# Wedding_Centerpiece_Controller_V1_0.net
KiCad netlist of a schematic drawn in EAGLE
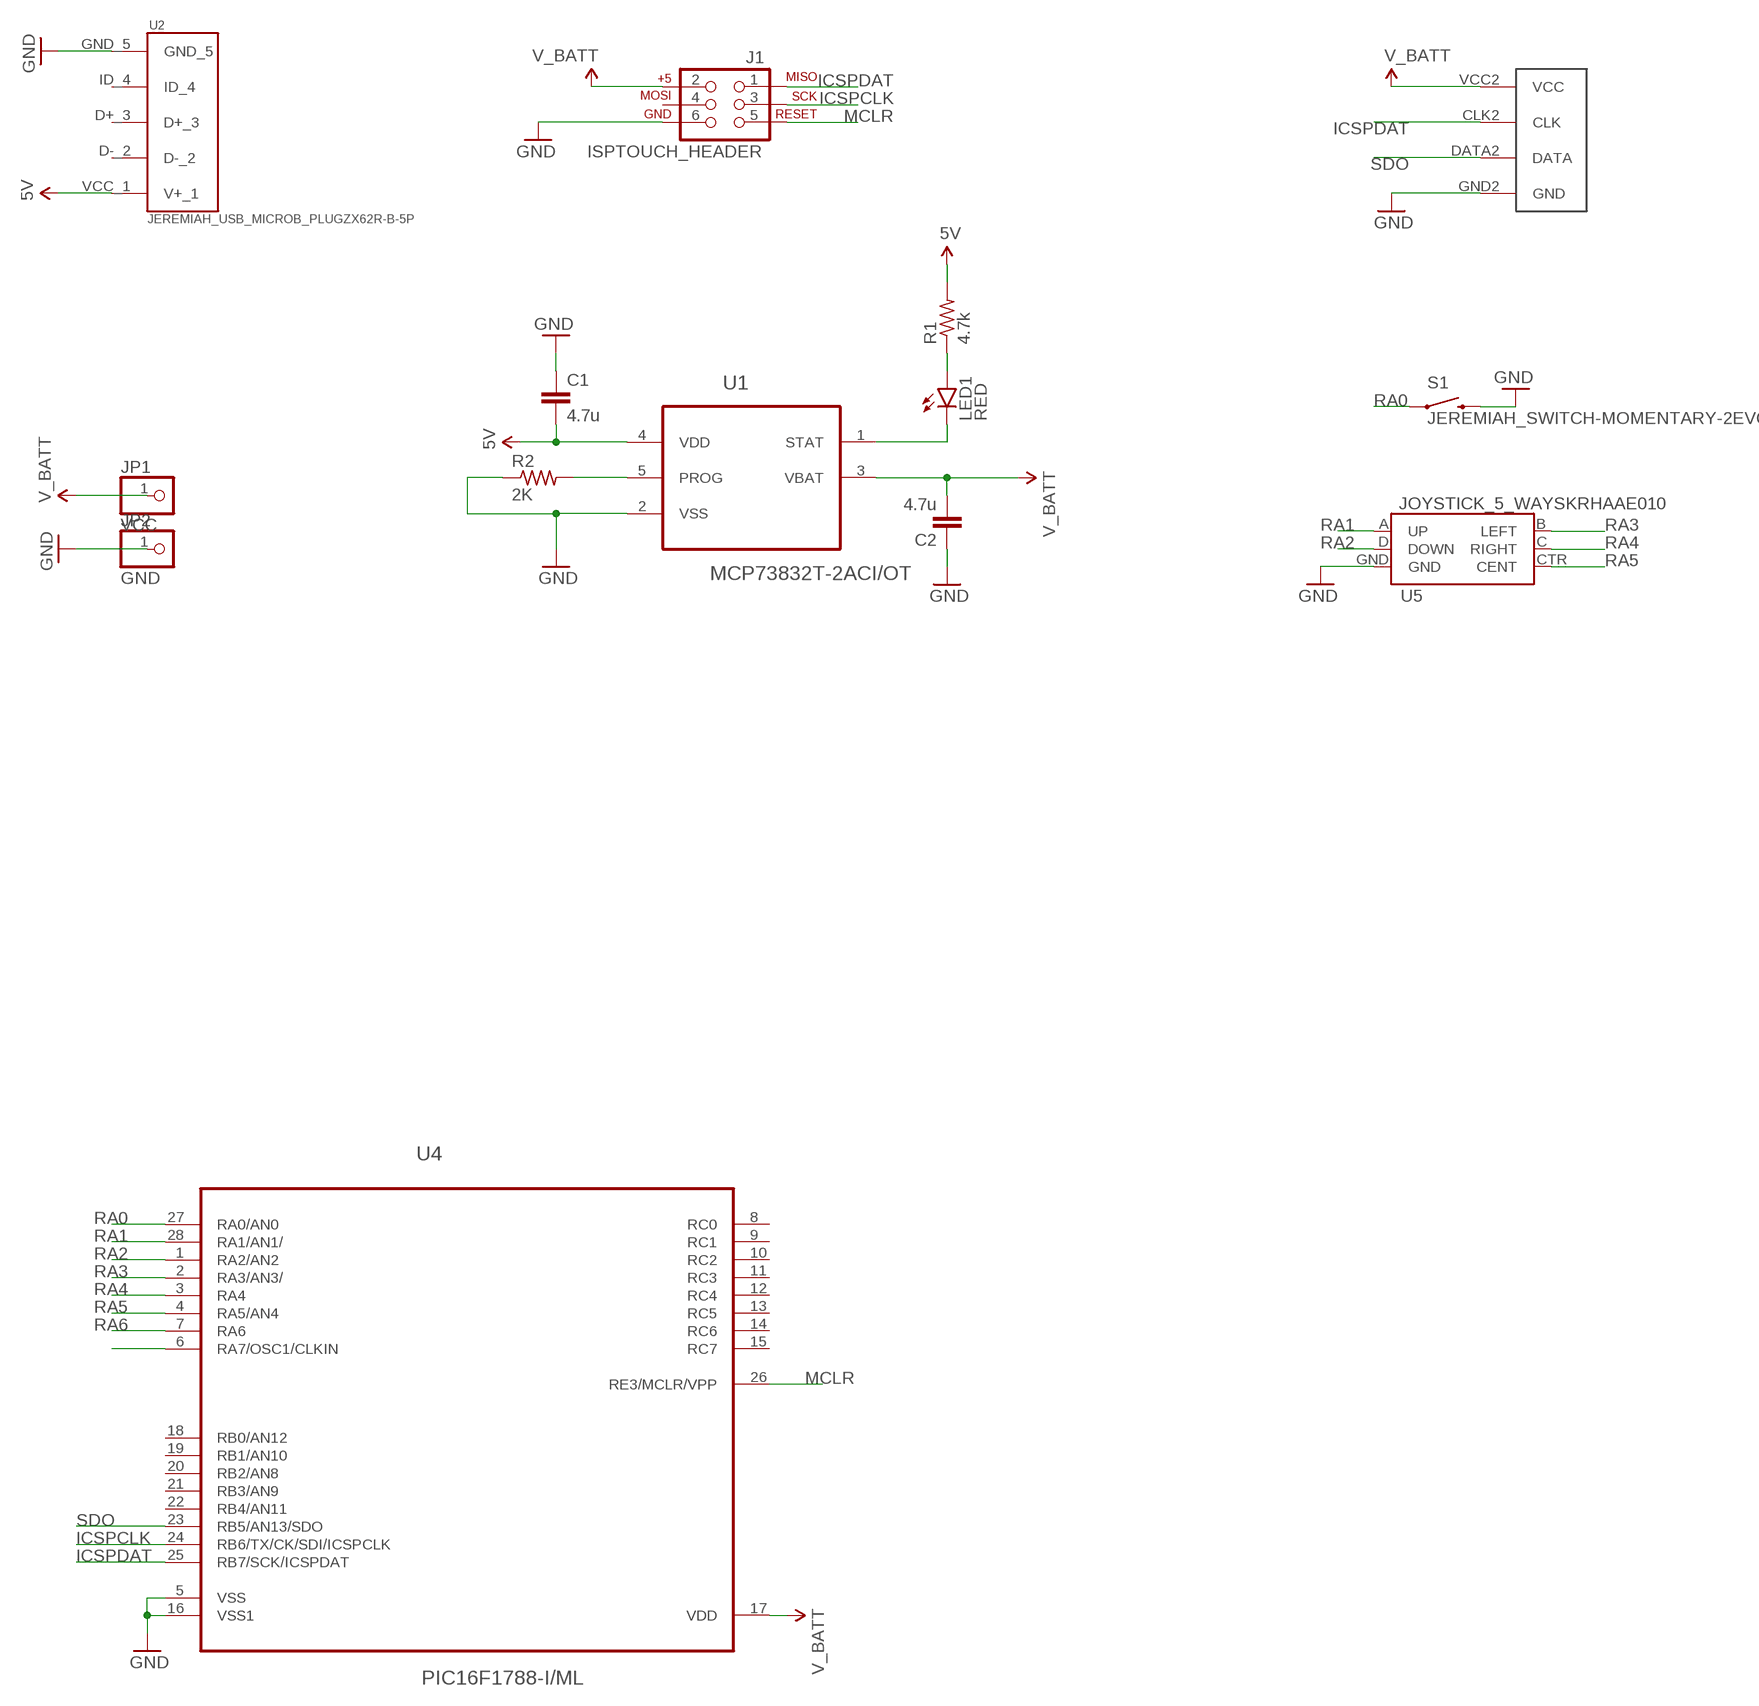
[diagram p0: schematic, sheet 1]

(export (version "E")
  (design (tool "Eeschema 10.0.6"))
  (components
    (comp (ref "C1")
      (value "4.7u")
      (footprint "eagle-import:0402-CAP")
      (libsource (lib "eagle-import") (part "CAP0402-CAP"))
    )
    (comp (ref "C2")
      (value "4.7u")
      (footprint "eagle-import:0402-CAP")
      (libsource (lib "eagle-import") (part "CAP0402-CAP"))
    )
    (comp (ref "J1")
      (value "ISPTOUCH_HEADER")
      (footprint "eagle-import:AVX_9188_6-WAY_MATING_GUIDE")
      (libsource (lib "eagle-import") (part "ISPTOUCH_HEADER"))
    )
    (comp (ref "JP1")
      (value "VCC")
      (footprint "eagle-import:1X01")
      (libsource (lib "eagle-import") (part "PINHD-1X1"))
    )
    (comp (ref "JP2")
      (value "GND")
      (footprint "eagle-import:1X01")
      (libsource (lib "eagle-import") (part "PINHD-1X1"))
    )
    (comp (ref "LED1")
      (value "RED")
      (footprint "eagle-import:LED-0603")
      (libsource (lib "eagle-import") (part "LED0603"))
    )
    (comp (ref "R1")
      (value "4.7k")
      (footprint "eagle-import:R0402")
      (libsource (lib "eagle-import") (part "R-US_R0402"))
    )
    (comp (ref "R2")
      (value "2K")
      (footprint "eagle-import:R0402")
      (libsource (lib "eagle-import") (part "R-US_R0402"))
    )
    (comp (ref "S1")
      (value "JEREMIAH_SWITCH-MOMENTARY-2EVQP4")
      (footprint "eagle-import:JEREMIAH_EVQP4_SWITCH")
      (libsource (lib "eagle-import") (part "JEREMIAH_SWITCH-MOMENTARY-2EVQP4"))
    )
    (comp (ref "U1")
      (value "MCP73832T-2ACI/OT")
      (footprint "eagle-import:SOT95P280X145-5N")
      (libsource (lib "eagle-import") (part "MCP73832T-2ACI/OT"))
    )
    (comp (ref "U2")
      (value "JEREMIAH_USB_MICROB_PLUGZX62R-B-5P")
      (footprint "eagle-import:JEREMIAH_USB_MICRO_ZX62R-B-5P")
      (libsource (lib "eagle-import") (part "JEREMIAH_USB_MICROB_PLUGZX62R-B-5P"))
    )
    (comp (ref "U3")
      (value "JEREMIAH_LED_STRIP_WS2801CLENLED_2L_BEGIN")
      (footprint "eagle-import:JEREMIAH_LED_STRIP_WS2801_CLENLED_2L_BEGIN")
      (libsource (lib "eagle-import") (part "JEREMIAH_LED_STRIP_WS2801CLENLED_2L_BEGIN"))
    )
    (comp (ref "U4")
      (value "PIC16F1788-I/ML")
      (footprint "eagle-import:QFN65P600X600X100-29N")
      (libsource (lib "eagle-import") (part "PIC16F1788-I/ML"))
    )
    (comp (ref "U5")
      (value "JOYSTICK_5_WAYSKRHAAE010")
      (footprint "eagle-import:ALPS_SKRHAAE010")
      (libsource (lib "eagle-import") (part "JOYSTICK_5_WAYSKRHAAE010"))
    )
  )
  (nets
    (net (code "1") (name "/ICSPCLK") (class "Default")
      (node (ref "J1") (pin "3") (pinfunction "3_3") (pintype "passive"))
      (node (ref "U4") (pin "24") (pinfunction "RB6/TX/CK/SDI/ICSPCLK_24") (pintype "bidirectional"))
    )
    (net (code "2") (name "/ICSPDAT") (class "Default")
      (node (ref "J1") (pin "1") (pinfunction "1_1") (pintype "passive"))
      (node (ref "U3") (pin "CLK2") (pinfunction "CLK_CLK2") (pintype "bidirectional"))
      (node (ref "U4") (pin "25") (pinfunction "RB7/SCK/ICSPDAT_25") (pintype "bidirectional"))
    )
    (net (code "3") (name "/MCLR") (class "Default")
      (node (ref "J1") (pin "5") (pinfunction "5_5") (pintype "passive"))
      (node (ref "U4") (pin "26") (pinfunction "RE3/MCLR/VPP_26") (pintype "bidirectional"))
    )
    (net (code "4") (name "/RA0") (class "Default")
      (node (ref "S1") (pin "1") (pinfunction "1_1") (pintype "passive"))
      (node (ref "U4") (pin "27") (pinfunction "RA0/AN0_27") (pintype "bidirectional"))
    )
    (net (code "5") (name "/RA1") (class "Default")
      (node (ref "U4") (pin "28") (pinfunction "RA1/AN1/_28") (pintype "bidirectional"))
      (node (ref "U5") (pin "A") (pinfunction "UP_A") (pintype "bidirectional"))
    )
    (net (code "6") (name "/RA2") (class "Default")
      (node (ref "U4") (pin "1") (pinfunction "RA2/AN2_1") (pintype "bidirectional"))
      (node (ref "U5") (pin "D") (pinfunction "DOWN_D") (pintype "bidirectional"))
    )
    (net (code "7") (name "/RA3") (class "Default")
      (node (ref "U4") (pin "2") (pinfunction "RA3/AN3/_2") (pintype "bidirectional"))
      (node (ref "U5") (pin "B") (pinfunction "LEFT_B") (pintype "bidirectional"))
    )
    (net (code "8") (name "/RA4") (class "Default")
      (node (ref "U4") (pin "3") (pinfunction "RA4_3") (pintype "bidirectional"))
      (node (ref "U5") (pin "C") (pinfunction "RIGHT_C") (pintype "bidirectional"))
    )
    (net (code "9") (name "/RA5") (class "Default")
      (node (ref "U4") (pin "4") (pinfunction "RA5/AN4_4") (pintype "input"))
      (node (ref "U5") (pin "CTR") (pinfunction "CENT_CTR") (pintype "bidirectional"))
    )
    (net (code "10") (name "/RA6") (class "Default")
      (node (ref "U4") (pin "7") (pinfunction "RA6_7") (pintype "bidirectional"))
    )
    (net (code "11") (name "/SDO") (class "Default")
      (node (ref "U3") (pin "DATA2") (pinfunction "DATA_DATA2") (pintype "bidirectional"))
      (node (ref "U4") (pin "23") (pinfunction "RB5/AN13/SDO_23") (pintype "bidirectional"))
    )
    (net (code "12") (name "5V") (class "Default")
      (node (ref "C1") (pin "2") (pinfunction "2_2") (pintype "passive"))
      (node (ref "R1") (pin "2") (pinfunction "2_2") (pintype "passive"))
      (node (ref "U1") (pin "4") (pinfunction "VDD_4") (pintype "power_in"))
      (node (ref "U2") (pin "VCC_1") (pinfunction "V+_1_VCC_1") (pintype "bidirectional"))
    )
    (net (code "13") (name "GND") (class "Default")
      (node (ref "C1") (pin "1") (pinfunction "1_1") (pintype "passive"))
      (node (ref "C2") (pin "1") (pinfunction "1_1") (pintype "passive"))
      (node (ref "J1") (pin "6") (pinfunction "6_6") (pintype "passive"))
      (node (ref "JP2") (pin "1") (pinfunction "1_1") (pintype "passive"))
      (node (ref "R2") (pin "1") (pinfunction "1_1") (pintype "passive"))
      (node (ref "S1") (pin "2") (pinfunction "2_2") (pintype "passive"))
      (node (ref "U1") (pin "2") (pinfunction "VSS_2") (pintype "power_in"))
      (node (ref "U2") (pin "GND_5") (pinfunction "GND_5_GND_5") (pintype "bidirectional"))
      (node (ref "U3") (pin "GND2") (pinfunction "GND_GND2") (pintype "bidirectional"))
      (node (ref "U4") (pin "16") (pinfunction "VSS1_16") (pintype "power_in"))
      (node (ref "U4") (pin "5") (pinfunction "VSS_5") (pintype "power_in"))
      (node (ref "U5") (pin "GND") (pinfunction "GND_GND") (pintype "bidirectional"))
    )
    (net (code "14") (name "Net-(LED1-PadA)") (class "Default")
      (node (ref "LED1") (pin "A") (pinfunction "A_A") (pintype "passive"))
      (node (ref "R1") (pin "1") (pinfunction "1_1") (pintype "passive"))
    )
    (net (code "15") (name "Net-(U1-PROG)") (class "Default")
      (node (ref "R2") (pin "2") (pinfunction "2_2") (pintype "passive"))
      (node (ref "U1") (pin "5") (pinfunction "PROG_5") (pintype "input"))
    )
    (net (code "16") (name "Net-(U1-STAT)") (class "Default")
      (node (ref "LED1") (pin "C") (pinfunction "C_C") (pintype "passive"))
      (node (ref "U1") (pin "1") (pinfunction "STAT_1") (pintype "output"))
    )
    (net (code "17") (name "V_BATT") (class "Default")
      (node (ref "C2") (pin "2") (pinfunction "2_2") (pintype "passive"))
      (node (ref "J1") (pin "2") (pinfunction "2_2") (pintype "passive"))
      (node (ref "JP1") (pin "1") (pinfunction "1_1") (pintype "passive"))
      (node (ref "U1") (pin "3") (pinfunction "VBAT_3") (pintype "output"))
      (node (ref "U3") (pin "VCC2") (pinfunction "VCC_VCC2") (pintype "bidirectional"))
      (node (ref "U4") (pin "17") (pinfunction "VDD_17") (pintype "power_in"))
    )
    (net (code "18") (name "unconnected-(J1-Pad4)") (class "Default")
      (node (ref "J1") (pin "4") (pinfunction "4_4") (pintype "passive"))
    )
    (net (code "19") (name "unconnected-(U2-PadD+_3)") (class "Default")
      (node (ref "U2") (pin "D+_3") (pinfunction "D+_3_D+_3") (pintype "bidirectional"))
    )
    (net (code "20") (name "unconnected-(U2-PadD-_2)") (class "Default")
      (node (ref "U2") (pin "D-_2") (pinfunction "D-_2_D-_2") (pintype "bidirectional"))
    )
    (net (code "21") (name "unconnected-(U2-PadID_4)") (class "Default")
      (node (ref "U2") (pin "ID_4") (pinfunction "ID_4_ID_4") (pintype "bidirectional"))
    )
    (net (code "22") (name "unconnected-(U4-RA7{slash}OSC1{slash}CLKIN-Pad6)") (class "Default")
      (node (ref "U4") (pin "6") (pinfunction "RA7/OSC1/CLKIN_6") (pintype "bidirectional"))
    )
    (net (code "23") (name "unconnected-(U4-RB0{slash}AN12-Pad18)") (class "Default")
      (node (ref "U4") (pin "18") (pinfunction "RB0/AN12_18") (pintype "bidirectional"))
    )
    (net (code "24") (name "unconnected-(U4-RB1{slash}AN10-Pad19)") (class "Default")
      (node (ref "U4") (pin "19") (pinfunction "RB1/AN10_19") (pintype "bidirectional"))
    )
    (net (code "25") (name "unconnected-(U4-RB2{slash}AN8-Pad20)") (class "Default")
      (node (ref "U4") (pin "20") (pinfunction "RB2/AN8_20") (pintype "bidirectional"))
    )
    (net (code "26") (name "unconnected-(U4-RB3{slash}AN9-Pad21)") (class "Default")
      (node (ref "U4") (pin "21") (pinfunction "RB3/AN9_21") (pintype "bidirectional"))
    )
    (net (code "27") (name "unconnected-(U4-RB4{slash}AN11-Pad22)") (class "Default")
      (node (ref "U4") (pin "22") (pinfunction "RB4/AN11_22") (pintype "bidirectional"))
    )
    (net (code "28") (name "unconnected-(U4-RC0-Pad8)") (class "Default")
      (node (ref "U4") (pin "8") (pinfunction "RC0_8") (pintype "bidirectional"))
    )
    (net (code "29") (name "unconnected-(U4-RC1-Pad9)") (class "Default")
      (node (ref "U4") (pin "9") (pinfunction "RC1_9") (pintype "bidirectional"))
    )
    (net (code "30") (name "unconnected-(U4-RC2-Pad10)") (class "Default")
      (node (ref "U4") (pin "10") (pinfunction "RC2_10") (pintype "bidirectional"))
    )
    (net (code "31") (name "unconnected-(U4-RC3-Pad11)") (class "Default")
      (node (ref "U4") (pin "11") (pinfunction "RC3_11") (pintype "bidirectional"))
    )
    (net (code "32") (name "unconnected-(U4-RC4-Pad12)") (class "Default")
      (node (ref "U4") (pin "12") (pinfunction "RC4_12") (pintype "bidirectional"))
    )
    (net (code "33") (name "unconnected-(U4-RC5-Pad13)") (class "Default")
      (node (ref "U4") (pin "13") (pinfunction "RC5_13") (pintype "bidirectional"))
    )
    (net (code "34") (name "unconnected-(U4-RC6-Pad14)") (class "Default")
      (node (ref "U4") (pin "14") (pinfunction "RC6_14") (pintype "bidirectional"))
    )
    (net (code "35") (name "unconnected-(U4-RC7-Pad15)") (class "Default")
      (node (ref "U4") (pin "15") (pinfunction "RC7_15") (pintype "bidirectional"))
    )
  )
)
